# untitled.net
KiCad netlist of a schematic drawn in EAGLE
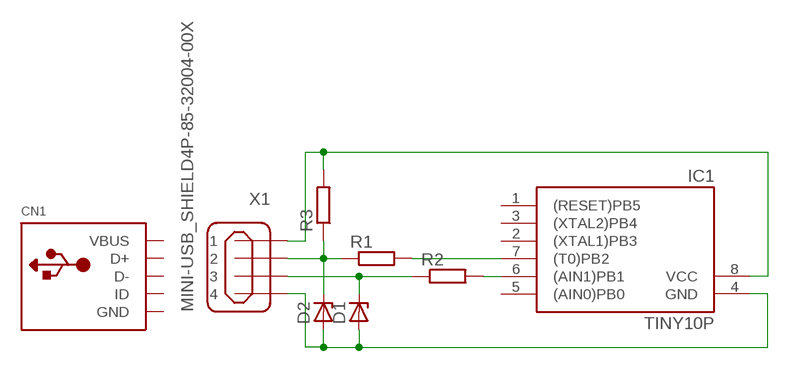
[diagram p0: schematic, sheet 1]

(export (version "E")
  (design (tool "Eeschema 10.0.6"))
  (components
    (comp (ref "CN1")
      (value "USBTHM")
      (footprint "eagle-import:USB-MINIB-THM")
      (libsource (lib "eagle-import") (part "USBTHM"))
    )
    (comp (ref "D1")
      (value "ZENER-DIODEZD-2.5")
      (footprint "eagle-import:ZDIO-2.5")
      (libsource (lib "eagle-import") (part "ZENER-DIODEZD-2.5"))
    )
    (comp (ref "D2")
      (value "ZENER-DIODEZD-5")
      (footprint "eagle-import:ZDIO-5")
      (libsource (lib "eagle-import") (part "ZENER-DIODEZD-5"))
    )
    (comp (ref "IC1")
      (value "TINY10P")
      (footprint "eagle-import:DIL08")
      (libsource (lib "eagle-import") (part "TINY10P"))
    )
    (comp (ref "R1")
      (value "R-EU_0204/2V")
      (footprint "eagle-import:0204V")
      (libsource (lib "eagle-import") (part "R-EU_0204/2V"))
    )
    (comp (ref "R2")
      (value "R-EU_0204/2V")
      (footprint "eagle-import:0204V")
      (libsource (lib "eagle-import") (part "R-EU_0204/2V"))
    )
    (comp (ref "R3")
      (value "R-EU_0204/2V")
      (footprint "eagle-import:0204V")
      (libsource (lib "eagle-import") (part "R-EU_0204/2V"))
    )
    (comp (ref "X1")
      (value "MINI-USB_SHIELD4P-85-32004-00X")
      (footprint "eagle-import:85-32004-00X")
      (libsource (lib "eagle-import") (part "MINI-USB_SHIELD4P-85-32004-00X"))
    )
  )
  (nets
    (net (code "1") (name "/GND") (class "Default")
      (node (ref "CN1") (pin "GND") (pinfunction "GND_GND") (pintype "power_in"))
    )
    (net (code "2") (name "/VBUS") (class "Default")
      (node (ref "CN1") (pin "VBUS") (pinfunction "VBUS_VBUS") (pintype "power_in"))
    )
    (net (code "3") (name "Net-(D1-PadC)") (class "Default")
      (node (ref "D1") (pin "C") (pinfunction "C_C") (pintype "passive"))
      (node (ref "R2") (pin "1") (pinfunction "1_1") (pintype "passive"))
      (node (ref "X1") (pin "3") (pinfunction "3_3") (pintype "passive"))
    )
    (net (code "4") (name "Net-(D2-PadC)") (class "Default")
      (node (ref "D2") (pin "C") (pinfunction "C_C") (pintype "passive"))
      (node (ref "R1") (pin "1") (pinfunction "1_1") (pintype "passive"))
      (node (ref "R3") (pin "1") (pinfunction "1_1") (pintype "passive"))
      (node (ref "X1") (pin "2") (pinfunction "2_2") (pintype "passive"))
    )
    (net (code "5") (name "Net-(IC1-(AIN1)PB1)") (class "Default")
      (node (ref "IC1") (pin "6") (pinfunction "(AIN1)PB1_6") (pintype "bidirectional"))
      (node (ref "R2") (pin "2") (pinfunction "2_2") (pintype "passive"))
    )
    (net (code "6") (name "Net-(IC1-(T0)PB2)") (class "Default")
      (node (ref "IC1") (pin "7") (pinfunction "(T0)PB2_7") (pintype "bidirectional"))
      (node (ref "R1") (pin "2") (pinfunction "2_2") (pintype "passive"))
    )
    (net (code "7") (name "Net-(IC1-GND)") (class "Default")
      (node (ref "D1") (pin "A") (pinfunction "A_A") (pintype "passive"))
      (node (ref "D2") (pin "A") (pinfunction "A_A") (pintype "passive"))
      (node (ref "IC1") (pin "4") (pinfunction "GND_4") (pintype "power_in"))
      (node (ref "X1") (pin "4") (pinfunction "4_4") (pintype "passive"))
    )
    (net (code "8") (name "Net-(IC1-VCC)") (class "Default")
      (node (ref "IC1") (pin "8") (pinfunction "VCC_8") (pintype "power_in"))
      (node (ref "R3") (pin "2") (pinfunction "2_2") (pintype "passive"))
      (node (ref "X1") (pin "1") (pinfunction "1_1") (pintype "passive"))
    )
    (net (code "9") (name "unconnected-(CN1-PadD+)") (class "Default")
      (node (ref "CN1") (pin "D+") (pinfunction "D+_D+") (pintype "bidirectional"))
    )
    (net (code "10") (name "unconnected-(CN1-PadD-)") (class "Default")
      (node (ref "CN1") (pin "D-") (pinfunction "D-_D-") (pintype "bidirectional"))
    )
    (net (code "11") (name "unconnected-(CN1-PadID)") (class "Default")
      (node (ref "CN1") (pin "ID") (pinfunction "ID_ID") (pintype "bidirectional"))
    )
    (net (code "12") (name "unconnected-(IC1-(AIN0)PB0-Pad5)") (class "Default")
      (node (ref "IC1") (pin "5") (pinfunction "(AIN0)PB0_5") (pintype "bidirectional"))
    )
    (net (code "13") (name "unconnected-(IC1-(RESET)PB5-Pad1)") (class "Default")
      (node (ref "IC1") (pin "1") (pinfunction "(RESET)PB5_1") (pintype "bidirectional"))
    )
    (net (code "14") (name "unconnected-(IC1-(XTAL1)PB3-Pad2)") (class "Default")
      (node (ref "IC1") (pin "2") (pinfunction "(XTAL1)PB3_2") (pintype "bidirectional"))
    )
    (net (code "15") (name "unconnected-(IC1-(XTAL2)PB4-Pad3)") (class "Default")
      (node (ref "IC1") (pin "3") (pinfunction "(XTAL2)PB4_3") (pintype "bidirectional"))
    )
  )
)
